# pymodel1.net
KiCad netlist of a schematic drawn in EAGLE
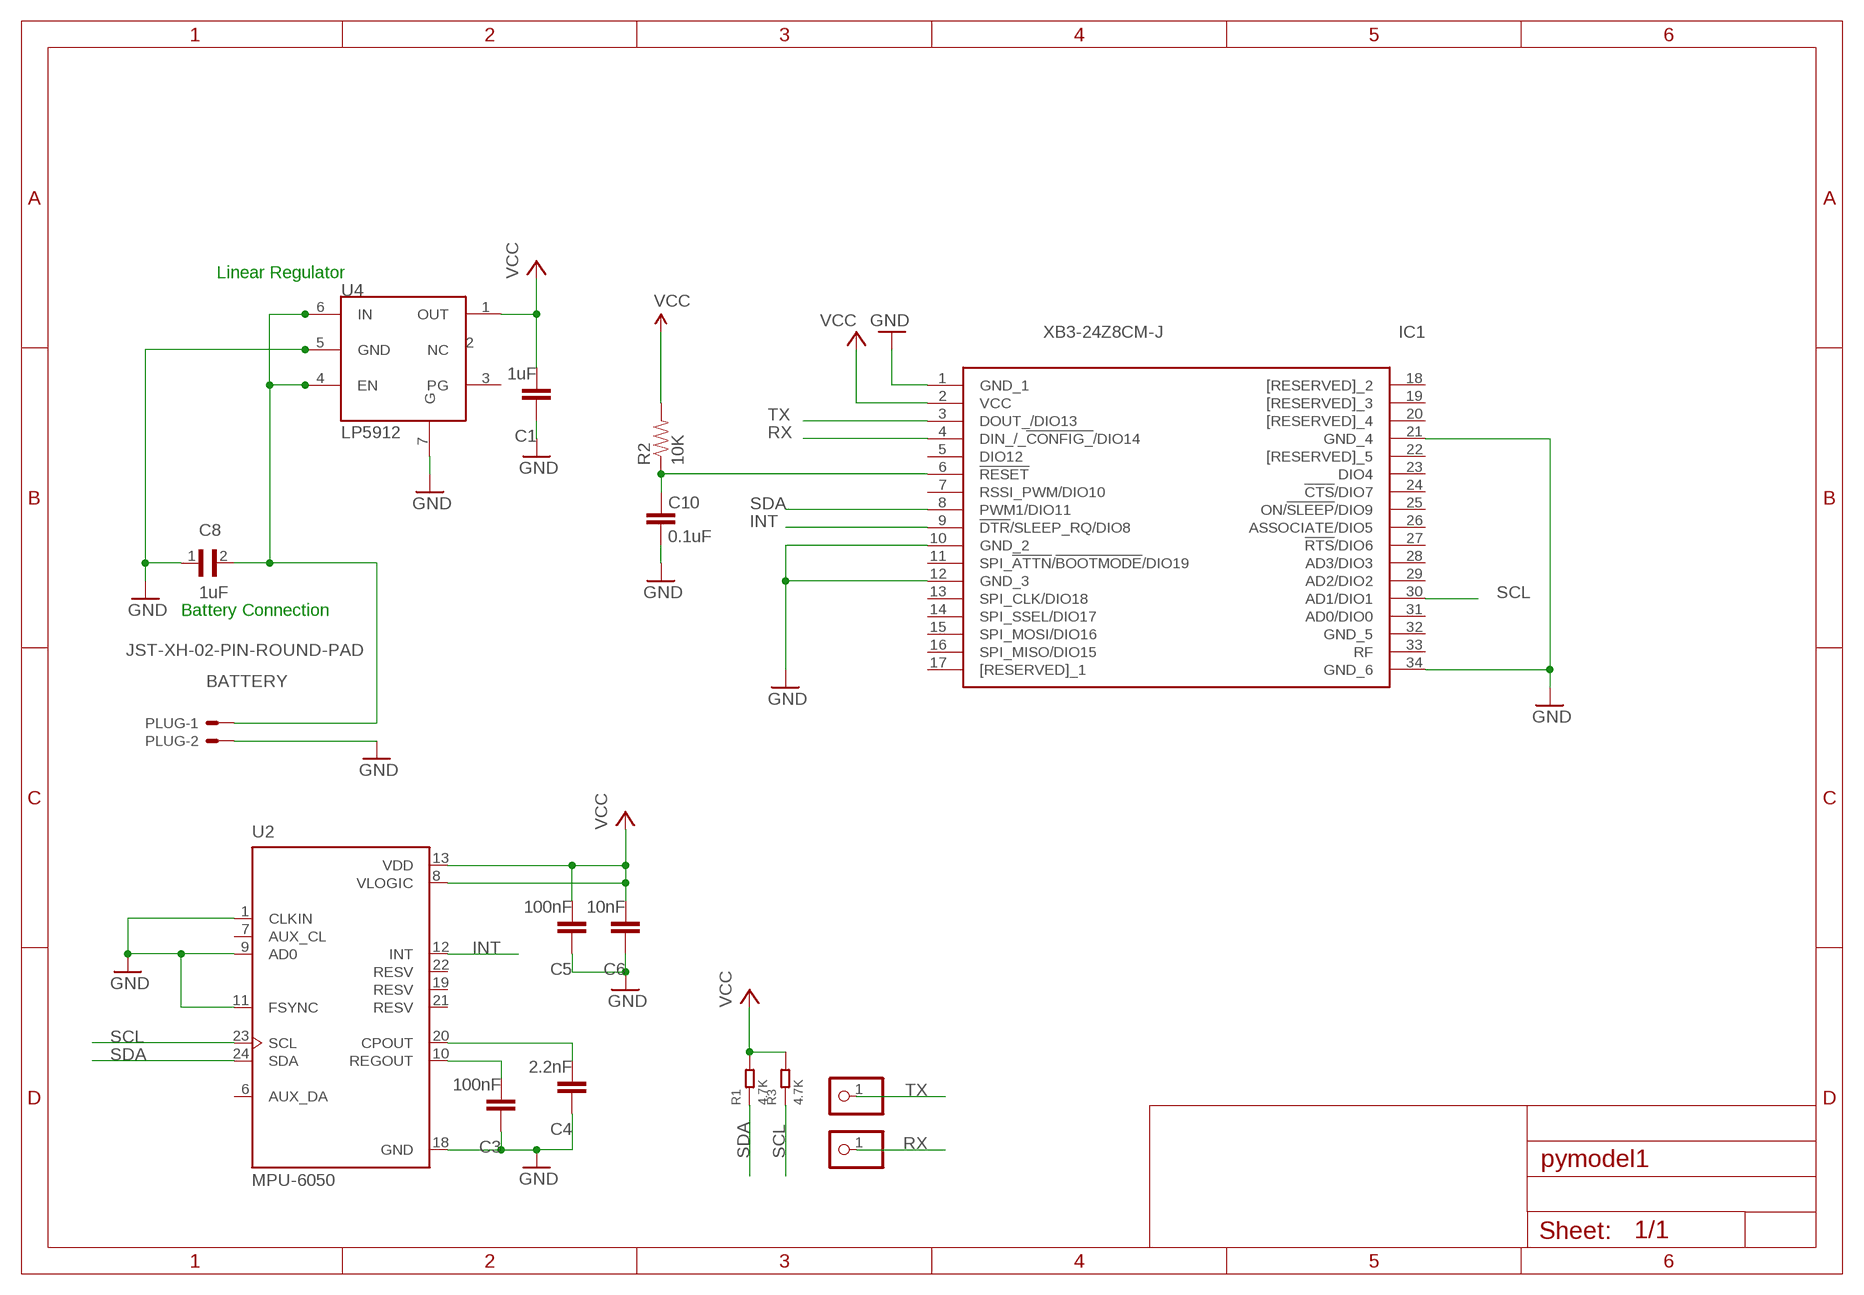
[diagram p0: schematic, sheet 1]

(export (version "E")
  (design (tool "Eeschema 10.0.6"))
  (components
    (comp (ref "C1")
      (value "1uF")
      (footprint "eagle-import:C0603")
      (libsource (lib "eagle-import") (part "C-EUC0603"))
    )
    (comp (ref "C3")
      (value "100nF")
      (footprint "eagle-import:C0603")
      (libsource (lib "eagle-import") (part "C-EUC0603"))
    )
    (comp (ref "C4")
      (value "2.2nF")
      (footprint "eagle-import:C0603")
      (libsource (lib "eagle-import") (part "C-EUC0603"))
    )
    (comp (ref "C5")
      (value "100nF")
      (footprint "eagle-import:C0603")
      (libsource (lib "eagle-import") (part "C-EUC0603"))
    )
    (comp (ref "C6")
      (value "10nF")
      (footprint "eagle-import:C0603")
      (libsource (lib "eagle-import") (part "C-EUC0603"))
    )
    (comp (ref "C8")
      (value "1uF")
      (footprint "eagle-import:CAPC1005X71N")
      (fields (field (name "MF") "AVX") (field (name "MP") "0402YD105MAT2A"))
      (libsource (lib "eagle-import") (part "0402YD105MAT2A"))
    )
    (comp (ref "C10")
      (value "0.1uF")
      (footprint "eagle-import:0603-CAP")
      (libsource (lib "eagle-import") (part "CAP0603-CAP"))
    )
    (comp (ref "IC1")
      (value "XB3-24Z8CM-J")
      (footprint "eagle-import:XB324Z8CMJ")
      (fields (field (name "MOUSER_PART_NUMBER") "888-XB3-24Z8CM-J"))
      (libsource (lib "eagle-import") (part "XB3-24Z8CM-J"))
    )
    (comp (ref "PLUG")
      (value "JST-XH-02-PIN-ROUND-PAD")
      (footprint "eagle-import:JST-XH-02-PACKAGE-ROUND-PAD")
      (libsource (lib "eagle-import") (part "JST-XH-02-PIN-ROUND-PAD"))
    )
    (comp (ref "R1")
      (value "4.7K")
      (footprint "eagle-import:R0402")
      (fields (field (name "MF") "Yageo") (field (name "MP") "RC0402JR074K7L"))
      (libsource (lib "eagle-import") (part "SMD-RES-4.7K-5%-1/16W(0402)"))
    )
    (comp (ref "R2")
      (value "10K")
      (footprint "eagle-import:0603-RES")
      (libsource (lib "eagle-import") (part "RESISTOR0603-RES"))
    )
    (comp (ref "R3")
      (value "4.7K")
      (footprint "eagle-import:R0402")
      (fields (field (name "MF") "Yageo") (field (name "MP") "RC0402JR074K7L"))
      (libsource (lib "eagle-import") (part "SMD-RES-4.7K-5%-1/16W(0402)"))
    )
    (comp (ref "RXX")
      (value "PINHD-1X1")
      (footprint "eagle-import:1X01")
      (libsource (lib "eagle-import") (part "PINHD-1X1"))
    )
    (comp (ref "TXX")
      (value "PINHD-1X1")
      (footprint "eagle-import:1X01")
      (libsource (lib "eagle-import") (part "PINHD-1X1"))
    )
    (comp (ref "U2")
      (value "MPU-6050")
      (footprint "eagle-import:QFN50P400X400X95-24N")
      (fields (field (name "MF") "TDK InvenSense"))
      (libsource (lib "eagle-import") (part "MPU-6050"))
    )
    (comp (ref "U4")
      (value "LP5912")
      (footprint "eagle-import:LP5912")
      (libsource (lib "eagle-import") (part "LP5912"))
    )
  )
  (nets
    (net (code "1") (name "/BATTERY") (class "Default")
      (node (ref "C8") (pin "2") (pinfunction "2_2") (pintype "passive"))
      (node (ref "PLUG") (pin "1") (pinfunction "S_1") (pintype "passive"))
      (node (ref "U4") (pin "4") (pinfunction "EN_4") (pintype "bidirectional"))
      (node (ref "U4") (pin "6") (pinfunction "IN_6") (pintype "power_in"))
    )
    (net (code "2") (name "/INT") (class "Default")
      (node (ref "IC1") (pin "9") (pinfunction "~{DTR}/SLEEP_RQ/DIO8_9") (pintype "bidirectional"))
      (node (ref "U2") (pin "12") (pinfunction "INT_12") (pintype "output"))
    )
    (net (code "3") (name "/RX") (class "Default")
      (node (ref "IC1") (pin "4") (pinfunction "DIN_/_~{CONFIG_}/DIO14_4") (pintype "bidirectional"))
      (node (ref "RXX") (pin "1") (pinfunction "1_1") (pintype "passive"))
    )
    (net (code "4") (name "/SCL") (class "Default")
      (node (ref "IC1") (pin "30") (pinfunction "AD1/DIO1_30") (pintype "bidirectional"))
      (node (ref "R3") (pin "1") (pinfunction "1_1") (pintype "passive"))
      (node (ref "U2") (pin "23") (pinfunction "SCL_23") (pintype "input"))
    )
    (net (code "5") (name "/SDA") (class "Default")
      (node (ref "IC1") (pin "8") (pinfunction "PWM1/DIO11_8") (pintype "bidirectional"))
      (node (ref "R1") (pin "1") (pinfunction "1_1") (pintype "passive"))
      (node (ref "U2") (pin "24") (pinfunction "SDA_24") (pintype "bidirectional"))
    )
    (net (code "6") (name "/TX") (class "Default")
      (node (ref "IC1") (pin "3") (pinfunction "DOUT_/DIO13_3") (pintype "bidirectional"))
      (node (ref "TXX") (pin "1") (pinfunction "1_1") (pintype "passive"))
    )
    (net (code "7") (name "GND") (class "Default")
      (node (ref "C1") (pin "1") (pinfunction "1_1") (pintype "passive"))
      (node (ref "C10") (pin "1") (pinfunction "1_1") (pintype "passive"))
      (node (ref "C3") (pin "1") (pinfunction "1_1") (pintype "passive"))
      (node (ref "C4") (pin "1") (pinfunction "1_1") (pintype "passive"))
      (node (ref "C5") (pin "1") (pinfunction "1_1") (pintype "passive"))
      (node (ref "C6") (pin "1") (pinfunction "1_1") (pintype "passive"))
      (node (ref "C8") (pin "1") (pinfunction "1_1") (pintype "passive"))
      (node (ref "IC1") (pin "1") (pinfunction "GND_1_1") (pintype "bidirectional"))
      (node (ref "IC1") (pin "10") (pinfunction "GND_2_10") (pintype "bidirectional"))
      (node (ref "IC1") (pin "12") (pinfunction "GND_3_12") (pintype "bidirectional"))
      (node (ref "IC1") (pin "21") (pinfunction "GND_4_21") (pintype "bidirectional"))
      (node (ref "IC1") (pin "34") (pinfunction "GND_6_34") (pintype "bidirectional"))
      (node (ref "PLUG") (pin "2") (pinfunction "S_2") (pintype "passive"))
      (node (ref "U2") (pin "1") (pinfunction "CLKIN_1") (pintype "input"))
      (node (ref "U2") (pin "11") (pinfunction "FSYNC_11") (pintype "input"))
      (node (ref "U2") (pin "18") (pinfunction "GND_18") (pintype "power_in"))
      (node (ref "U2") (pin "9") (pinfunction "AD0_9") (pintype "input"))
      (node (ref "U4") (pin "5") (pinfunction "GND_5") (pintype "power_in"))
      (node (ref "U4") (pin "7") (pinfunction "G_7") (pintype "bidirectional"))
    )
    (net (code "8") (name "Net-(IC1-~{RESET})") (class "Default")
      (node (ref "C10") (pin "2") (pinfunction "2_2") (pintype "passive"))
      (node (ref "IC1") (pin "6") (pinfunction "~{RESET}_6") (pintype "bidirectional"))
      (node (ref "R2") (pin "1") (pinfunction "1_1") (pintype "passive"))
    )
    (net (code "9") (name "Net-(U2-CPOUT)") (class "Default")
      (node (ref "C4") (pin "2") (pinfunction "2_2") (pintype "passive"))
      (node (ref "U2") (pin "20") (pinfunction "CPOUT_20") (pintype "passive"))
    )
    (net (code "10") (name "Net-(U2-REGOUT)") (class "Default")
      (node (ref "C3") (pin "2") (pinfunction "2_2") (pintype "passive"))
      (node (ref "U2") (pin "10") (pinfunction "REGOUT_10") (pintype "passive"))
    )
    (net (code "11") (name "VCC") (class "Default")
      (node (ref "C1") (pin "2") (pinfunction "2_2") (pintype "passive"))
      (node (ref "C5") (pin "2") (pinfunction "2_2") (pintype "passive"))
      (node (ref "C6") (pin "2") (pinfunction "2_2") (pintype "passive"))
      (node (ref "IC1") (pin "2") (pinfunction "VCC_2") (pintype "bidirectional"))
      (node (ref "R1") (pin "2") (pinfunction "2_2") (pintype "passive"))
      (node (ref "R2") (pin "2") (pinfunction "2_2") (pintype "passive"))
      (node (ref "R3") (pin "2") (pinfunction "2_2") (pintype "passive"))
      (node (ref "U2") (pin "13") (pinfunction "VDD_13") (pintype "power_in"))
      (node (ref "U2") (pin "8") (pinfunction "VLOGIC_8") (pintype "power_in"))
      (node (ref "U4") (pin "1") (pinfunction "OUT_1") (pintype "power_in"))
    )
    (net (code "12") (name "unconnected-(IC1-AD0{slash}DIO0-Pad31)") (class "Default")
      (node (ref "IC1") (pin "31") (pinfunction "AD0/DIO0_31") (pintype "bidirectional"))
    )
    (net (code "13") (name "unconnected-(IC1-AD2{slash}DIO2-Pad29)") (class "Default")
      (node (ref "IC1") (pin "29") (pinfunction "AD2/DIO2_29") (pintype "bidirectional"))
    )
    (net (code "14") (name "unconnected-(IC1-AD3{slash}DIO3-Pad28)") (class "Default")
      (node (ref "IC1") (pin "28") (pinfunction "AD3/DIO3_28") (pintype "bidirectional"))
    )
    (net (code "15") (name "unconnected-(IC1-ASSOCIATE{slash}DIO5-Pad26)") (class "Default")
      (node (ref "IC1") (pin "26") (pinfunction "ASSOCIATE/DIO5_26") (pintype "bidirectional"))
    )
    (net (code "16") (name "unconnected-(IC1-DIO4-Pad23)") (class "Default")
      (node (ref "IC1") (pin "23") (pinfunction "DIO4_23") (pintype "bidirectional"))
    )
    (net (code "17") (name "unconnected-(IC1-DIO12-Pad5)") (class "Default")
      (node (ref "IC1") (pin "5") (pinfunction "DIO12_5") (pintype "bidirectional"))
    )
    (net (code "18") (name "unconnected-(IC1-GND_5-Pad32)") (class "Default")
      (node (ref "IC1") (pin "32") (pinfunction "GND_5_32") (pintype "bidirectional"))
    )
    (net (code "19") (name "unconnected-(IC1-ON{slash}~{SLEEP}{slash}DIO9-Pad25)") (class "Default")
      (node (ref "IC1") (pin "25") (pinfunction "ON/~{SLEEP}/DIO9_25") (pintype "bidirectional"))
    )
    (net (code "20") (name "unconnected-(IC1-RF-Pad33)") (class "Default")
      (node (ref "IC1") (pin "33") (pinfunction "RF_33") (pintype "bidirectional"))
    )
    (net (code "21") (name "unconnected-(IC1-RSSI_PWM{slash}DIO10-Pad7)") (class "Default")
      (node (ref "IC1") (pin "7") (pinfunction "RSSI_PWM/DIO10_7") (pintype "bidirectional"))
    )
    (net (code "22") (name "unconnected-(IC1-SPI_CLK{slash}DIO18-Pad13)") (class "Default")
      (node (ref "IC1") (pin "13") (pinfunction "SPI_CLK/DIO18_13") (pintype "bidirectional"))
    )
    (net (code "23") (name "unconnected-(IC1-SPI_MISO{slash}DIO15-Pad16)") (class "Default")
      (node (ref "IC1") (pin "16") (pinfunction "SPI_MISO/DIO15_16") (pintype "bidirectional"))
    )
    (net (code "24") (name "unconnected-(IC1-SPI_MOSI{slash}DIO16-Pad15)") (class "Default")
      (node (ref "IC1") (pin "15") (pinfunction "SPI_MOSI/DIO16_15") (pintype "bidirectional"))
    )
    (net (code "25") (name "unconnected-(IC1-SPI_SSEL{slash}DIO17-Pad14)") (class "Default")
      (node (ref "IC1") (pin "14") (pinfunction "SPI_SSEL/DIO17_14") (pintype "bidirectional"))
    )
    (net (code "26") (name "unconnected-(IC1-SPI_~{ATTN}{slash}~{BOOTMODE}{slash}DIO19-Pad11)") (class "Default")
      (node (ref "IC1") (pin "11") (pinfunction "SPI_~{ATTN}/~{BOOTMODE}/DIO19_11") (pintype "bidirectional"))
    )
    (net (code "27") (name "unconnected-(IC1-[RESERVED]_1-Pad17)") (class "Default")
      (node (ref "IC1") (pin "17") (pinfunction "[RESERVED]_1_17") (pintype "bidirectional"))
    )
    (net (code "28") (name "unconnected-(IC1-[RESERVED]_2-Pad18)") (class "Default")
      (node (ref "IC1") (pin "18") (pinfunction "[RESERVED]_2_18") (pintype "bidirectional"))
    )
    (net (code "29") (name "unconnected-(IC1-[RESERVED]_3-Pad19)") (class "Default")
      (node (ref "IC1") (pin "19") (pinfunction "[RESERVED]_3_19") (pintype "bidirectional"))
    )
    (net (code "30") (name "unconnected-(IC1-[RESERVED]_4-Pad20)") (class "Default")
      (node (ref "IC1") (pin "20") (pinfunction "[RESERVED]_4_20") (pintype "bidirectional"))
    )
    (net (code "31") (name "unconnected-(IC1-[RESERVED]_5-Pad22)") (class "Default")
      (node (ref "IC1") (pin "22") (pinfunction "[RESERVED]_5_22") (pintype "bidirectional"))
    )
    (net (code "32") (name "unconnected-(IC1-~{CTS}{slash}DIO7-Pad24)") (class "Default")
      (node (ref "IC1") (pin "24") (pinfunction "~{CTS}/DIO7_24") (pintype "bidirectional"))
    )
    (net (code "33") (name "unconnected-(IC1-~{RTS}{slash}DIO6-Pad27)") (class "Default")
      (node (ref "IC1") (pin "27") (pinfunction "~{RTS}/DIO6_27") (pintype "bidirectional"))
    )
    (net (code "34") (name "unconnected-(U2-AUX_CL-Pad7)") (class "Default")
      (node (ref "U2") (pin "7") (pinfunction "AUX_CL_7") (pintype "input"))
    )
    (net (code "35") (name "unconnected-(U2-AUX_DA-Pad6)") (class "Default")
      (node (ref "U2") (pin "6") (pinfunction "AUX_DA_6") (pintype "bidirectional"))
    )
    (net (code "36") (name "unconnected-(U2-RESV-Pad19)") (class "Default")
      (node (ref "U2") (pin "19") (pinfunction "RESV_19") (pintype "passive"))
    )
    (net (code "37") (name "unconnected-(U2-RESV-Pad21)") (class "Default")
      (node (ref "U2") (pin "21") (pinfunction "RESV_21") (pintype "passive"))
    )
    (net (code "38") (name "unconnected-(U2-RESV-Pad22)") (class "Default")
      (node (ref "U2") (pin "22") (pinfunction "RESV_22") (pintype "passive"))
    )
    (net (code "39") (name "unconnected-(U4-NC-Pad2)") (class "Default")
      (node (ref "U4") (pin "2") (pinfunction "NC_2") (pintype "bidirectional"))
    )
    (net (code "40") (name "unconnected-(U4-PG-Pad3)") (class "Default")
      (node (ref "U4") (pin "3") (pinfunction "PG_3") (pintype "bidirectional"))
    )
  )
)
